# AIRDCL.net
KiCad netlist of a schematic drawn in EAGLE
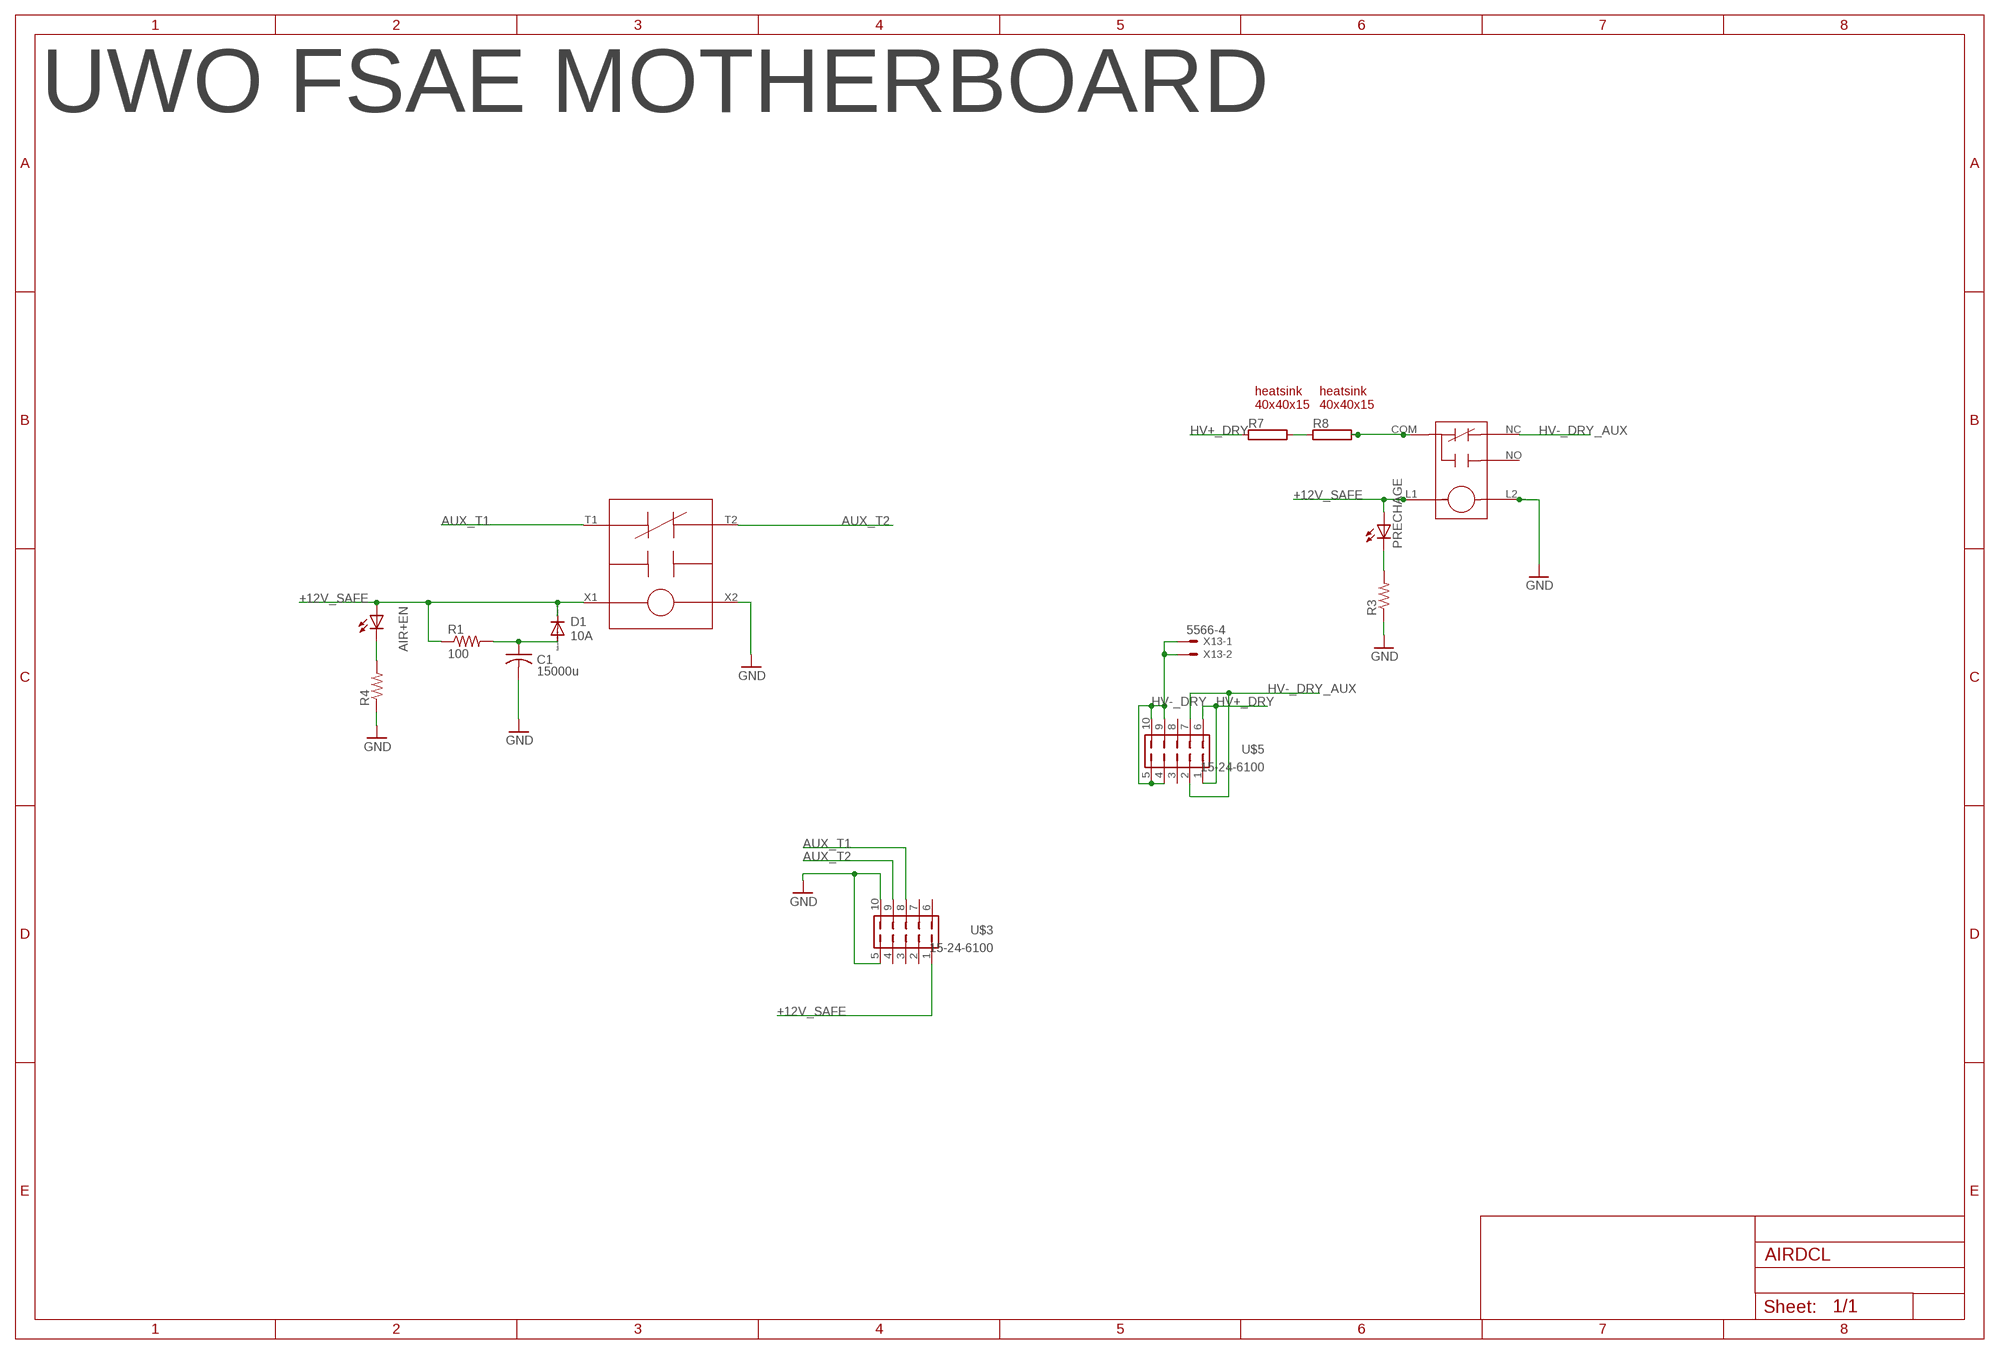
[diagram p0: schematic, sheet 1]

(export (version "E")
  (design (tool "Eeschema 10.0.6"))
  (components
    (comp (ref "AIR+EN")
      (value "LED3MM")
      (footprint "eagle-import:LED3MM")
      (libsource (lib "eagle-import") (part "LED3MM"))
    )
    (comp (ref "C1")
      (value "15000u")
      (footprint "eagle-import:CAPPRD750W65D1800H3700B")
      (libsource (lib "eagle-import") (part "AIR_HOLDUP_CAP"))
    )
    (comp (ref "D1")
      (value "10A")
      (footprint "eagle-import:DIOAD1570W120L850D500B")
      (libsource (lib "eagle-import") (part "AIR_HOLDUP_DIODE"))
    )
    (comp (ref "PRECHAGE")
      (value "LED3MM")
      (footprint "eagle-import:LED3MM")
      (libsource (lib "eagle-import") (part "LED3MM"))
    )
    (comp (ref "R1")
      (value "100")
      (footprint "eagle-import:RESAD976W63L650D250B")
      (libsource (lib "eagle-import") (part "AIR_HOLDUP_RESISTOR"))
    )
    (comp (ref "R3")
      (value "R-US_R0805")
      (footprint "eagle-import:R0805")
      (libsource (lib "eagle-import") (part "R-US_R0805"))
    )
    (comp (ref "R4")
      (value "R-US_R0805")
      (footprint "eagle-import:R0805")
      (libsource (lib "eagle-import") (part "R-US_R0805"))
    )
    (comp (ref "R7")
      (value "RMG100-H")
      (footprint "eagle-import:TO-247-2H")
      (libsource (lib "eagle-import") (part "RMG100-H"))
    )
    (comp (ref "R8")
      (value "RMG100-H")
      (footprint "eagle-import:TO-247-2H")
      (libsource (lib "eagle-import") (part "RMG100-H"))
    )
    (comp (ref "U$1")
      (value "GV224")
      (footprint "eagle-import:GV224")
      (libsource (lib "eagle-import") (part "GV224"))
    )
    (comp (ref "U$2")
      (value "HEATSINK40X40X15")
      (footprint "eagle-import:HEATSINK40X40X15")
      (libsource (lib "eagle-import") (part "HEATSINK40X40X15"))
    )
    (comp (ref "U$3")
      (value "15-24-6100")
      (footprint "eagle-import:15-24-6100")
      (libsource (lib "eagle-import") (part "15-24-6100"))
    )
    (comp (ref "U$4")
      (value "G81C335")
      (footprint "eagle-import:G81C335")
      (libsource (lib "eagle-import") (part "G81C335"))
    )
    (comp (ref "U$5")
      (value "15-24-6100")
      (footprint "eagle-import:15-24-6100")
      (libsource (lib "eagle-import") (part "15-24-6100"))
    )
    (comp (ref "U$8")
      (value "HEATSINK40X40X15")
      (footprint "eagle-import:HEATSINK40X40X15")
      (libsource (lib "eagle-import") (part "HEATSINK40X40X15"))
    )
    (comp (ref "X13")
      (value "5566-4")
      (footprint "eagle-import:5566-4")
      (fields (field (name "MF") "MOLEX"))
      (libsource (lib "eagle-import") (part "5566-4"))
    )
  )
  (nets
    (net (code "1") (name "/+12V_SAFE") (class "Default")
      (node (ref "AIR+EN") (pin "A") (pinfunction "A_A") (pintype "passive"))
      (node (ref "D1") (pin "1") (pinfunction "C_1") (pintype "passive"))
      (node (ref "PRECHAGE") (pin "A") (pinfunction "A_A") (pintype "passive"))
      (node (ref "R1") (pin "1") (pinfunction "1_1") (pintype "passive"))
      (node (ref "U$1") (pin "X1") (pinfunction "X1_X1") (pintype "bidirectional"))
      (node (ref "U$3") (pin "1") (pinfunction "1_1") (pintype "passive"))
      (node (ref "U$4") (pin "L1") (pinfunction "L1_L1") (pintype "bidirectional"))
    )
    (net (code "2") (name "/AUX_T1") (class "Default")
      (node (ref "U$1") (pin "T1") (pinfunction "T1_T1") (pintype "bidirectional"))
      (node (ref "U$3") (pin "8") (pinfunction "8_8") (pintype "passive"))
    )
    (net (code "3") (name "/AUX_T2") (class "Default")
      (node (ref "U$1") (pin "T2") (pinfunction "T2_T2") (pintype "bidirectional"))
      (node (ref "U$3") (pin "9") (pinfunction "9_9") (pintype "passive"))
    )
    (net (code "4") (name "/HV+_DRY") (class "Default")
      (node (ref "R7") (pin "1") (pinfunction "1_1") (pintype "passive"))
      (node (ref "U$5") (pin "1") (pinfunction "1_1") (pintype "passive"))
      (node (ref "U$5") (pin "6") (pinfunction "6_6") (pintype "passive"))
    )
    (net (code "5") (name "/HV-_DRY") (class "Default")
      (node (ref "U$5") (pin "10") (pinfunction "10_10") (pintype "passive"))
      (node (ref "U$5") (pin "4") (pinfunction "4_4") (pintype "passive"))
      (node (ref "U$5") (pin "5") (pinfunction "5_5") (pintype "passive"))
      (node (ref "U$5") (pin "9") (pinfunction "9_9") (pintype "passive"))
      (node (ref "X13") (pin "1") (pinfunction "S_1") (pintype "passive"))
      (node (ref "X13") (pin "2") (pinfunction "S_2") (pintype "passive"))
    )
    (net (code "6") (name "/HV-_DRY_AUX") (class "Default")
      (node (ref "U$4") (pin "NC") (pinfunction "NC_NC") (pintype "bidirectional"))
      (node (ref "U$5") (pin "2") (pinfunction "2_2") (pintype "passive"))
      (node (ref "U$5") (pin "7") (pinfunction "7_7") (pintype "passive"))
    )
    (net (code "7") (name "GND") (class "Default")
      (node (ref "C1") (pin "2") (pinfunction "2_2") (pintype "passive"))
      (node (ref "R3") (pin "1") (pinfunction "1_1") (pintype "passive"))
      (node (ref "R4") (pin "1") (pinfunction "1_1") (pintype "passive"))
      (node (ref "U$1") (pin "X2") (pinfunction "X2_X2") (pintype "bidirectional"))
      (node (ref "U$3") (pin "10") (pinfunction "10_10") (pintype "passive"))
      (node (ref "U$3") (pin "5") (pinfunction "5_5") (pintype "passive"))
      (node (ref "U$4") (pin "L2") (pinfunction "L2_L2") (pintype "bidirectional"))
    )
    (net (code "8") (name "Net-(AIR+EN-C)") (class "Default")
      (node (ref "AIR+EN") (pin "K") (pinfunction "C_K") (pintype "passive"))
      (node (ref "R4") (pin "2") (pinfunction "2_2") (pintype "passive"))
    )
    (net (code "9") (name "Net-(D1-A)") (class "Default")
      (node (ref "C1") (pin "1") (pinfunction "1_1") (pintype "passive"))
      (node (ref "D1") (pin "2") (pinfunction "A_2") (pintype "passive"))
      (node (ref "R1") (pin "2") (pinfunction "2_2") (pintype "passive"))
    )
    (net (code "10") (name "Net-(PRECHAGE-C)") (class "Default")
      (node (ref "PRECHAGE") (pin "K") (pinfunction "C_K") (pintype "passive"))
      (node (ref "R3") (pin "2") (pinfunction "2_2") (pintype "passive"))
    )
    (net (code "11") (name "Net-(R7-Pad2)") (class "Default")
      (node (ref "R7") (pin "2") (pinfunction "2_2") (pintype "passive"))
      (node (ref "R8") (pin "1") (pinfunction "1_1") (pintype "passive"))
    )
    (net (code "12") (name "Net-(R8-Pad2)") (class "Default")
      (node (ref "R8") (pin "2") (pinfunction "2_2") (pintype "passive"))
      (node (ref "U$4") (pin "COM") (pinfunction "COM_COM") (pintype "bidirectional"))
    )
    (net (code "13") (name "unconnected-(U$3-Pad2)") (class "Default")
      (node (ref "U$3") (pin "2") (pinfunction "2_2") (pintype "passive"))
    )
    (net (code "14") (name "unconnected-(U$3-Pad3)") (class "Default")
      (node (ref "U$3") (pin "3") (pinfunction "3_3") (pintype "passive"))
    )
    (net (code "15") (name "unconnected-(U$3-Pad4)") (class "Default")
      (node (ref "U$3") (pin "4") (pinfunction "4_4") (pintype "passive"))
    )
    (net (code "16") (name "unconnected-(U$3-Pad6)") (class "Default")
      (node (ref "U$3") (pin "6") (pinfunction "6_6") (pintype "passive"))
    )
    (net (code "17") (name "unconnected-(U$3-Pad7)") (class "Default")
      (node (ref "U$3") (pin "7") (pinfunction "7_7") (pintype "passive"))
    )
    (net (code "18") (name "unconnected-(U$4-PadNO)") (class "Default")
      (node (ref "U$4") (pin "NO") (pinfunction "NO_NO") (pintype "bidirectional"))
    )
    (net (code "19") (name "unconnected-(U$5-Pad3)") (class "Default")
      (node (ref "U$5") (pin "3") (pinfunction "3_3") (pintype "passive"))
    )
    (net (code "20") (name "unconnected-(U$5-Pad8)") (class "Default")
      (node (ref "U$5") (pin "8") (pinfunction "8_8") (pintype "passive"))
    )
  )
)
